# node.net
KiCad netlist of a schematic drawn in EAGLE
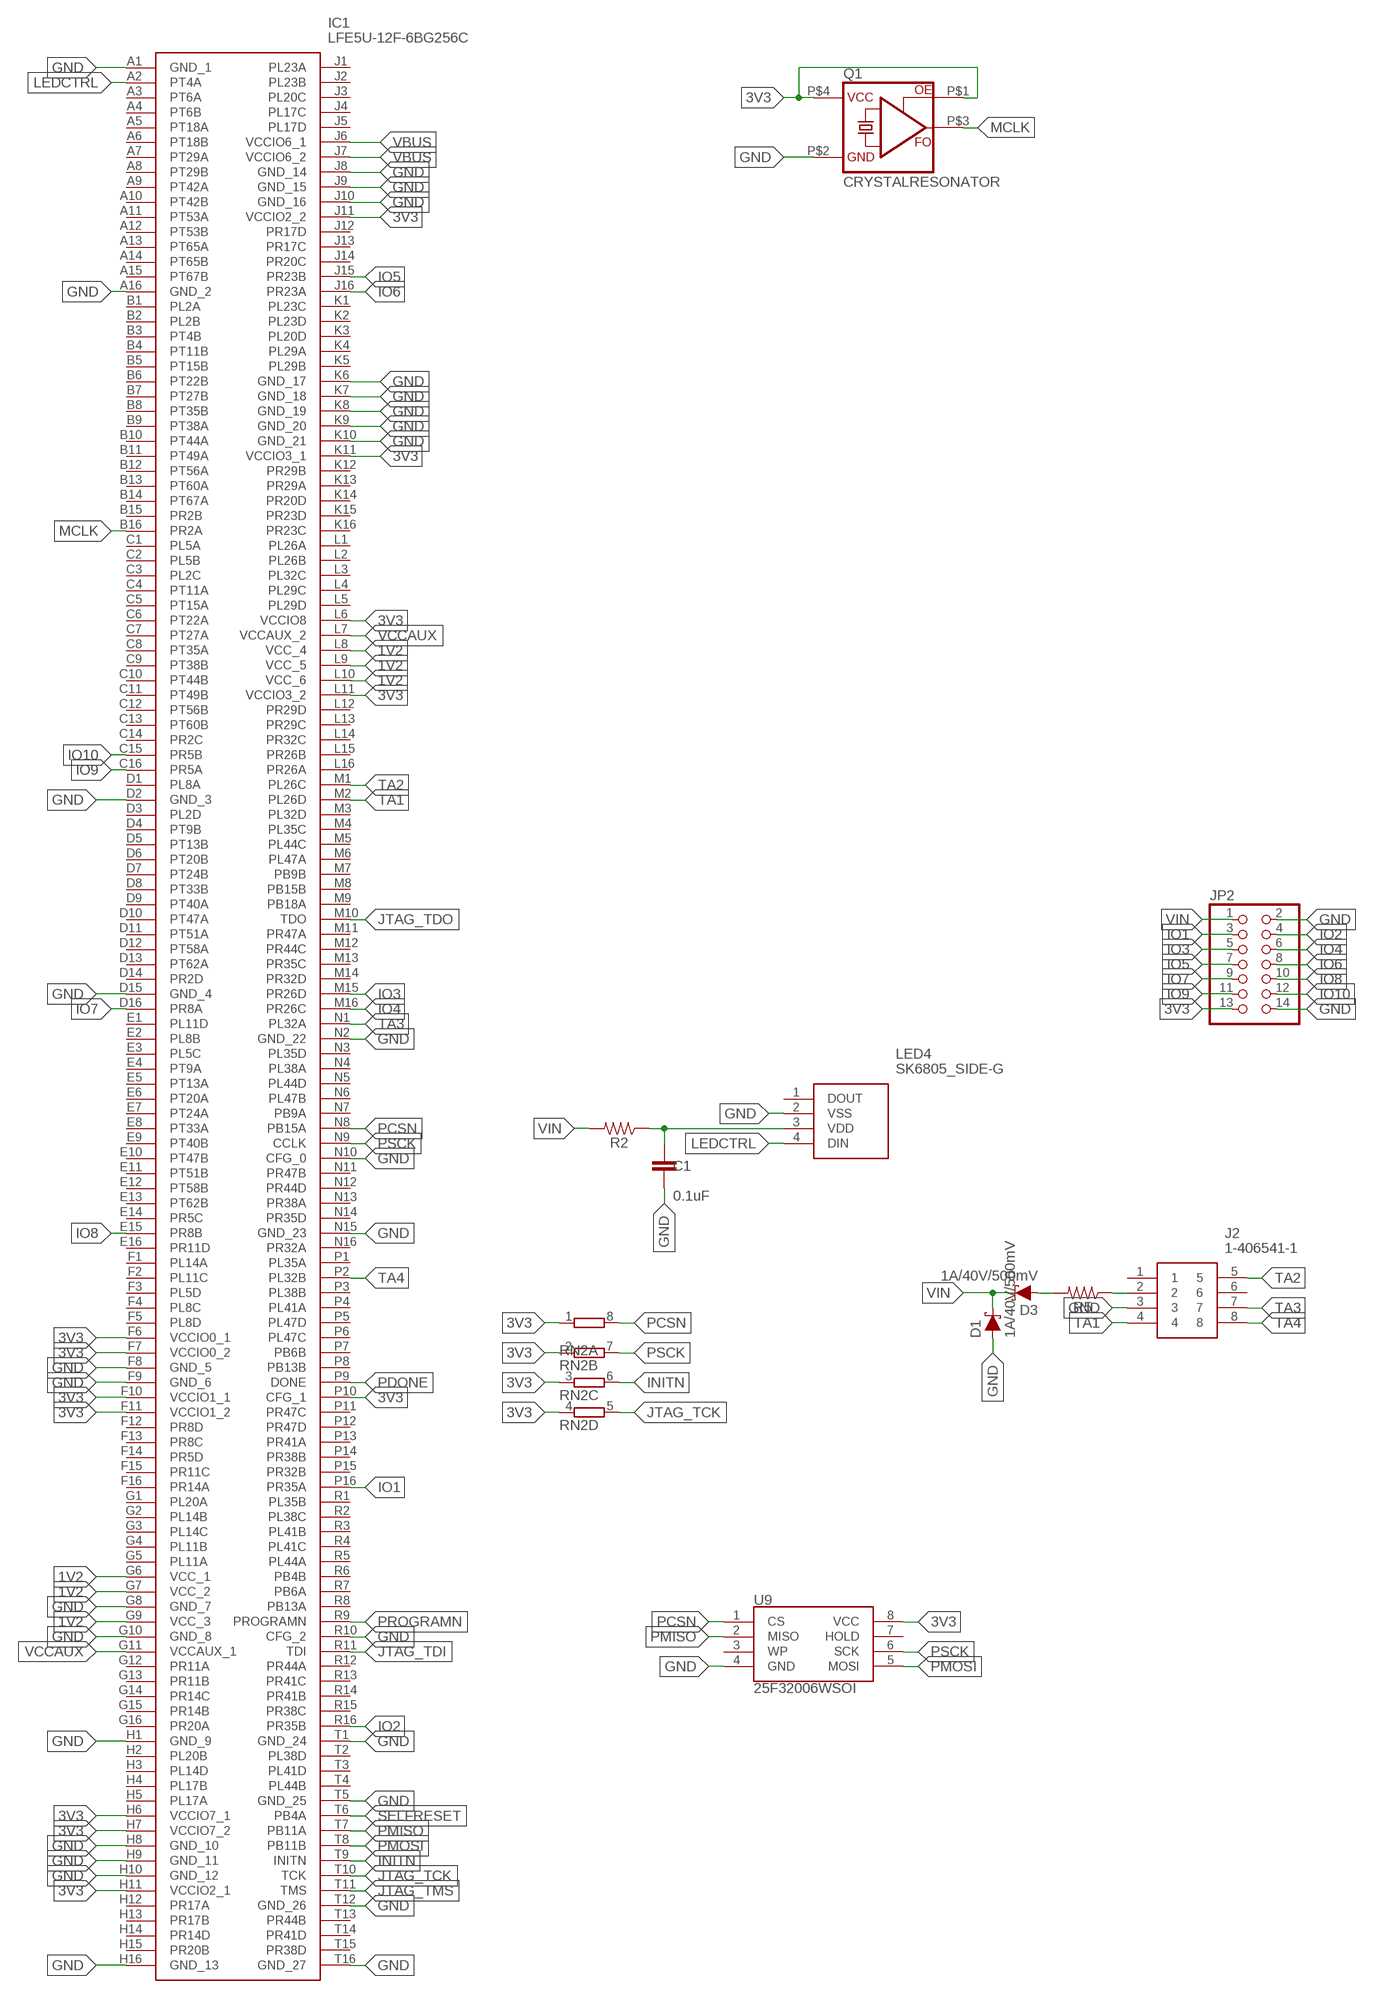
[diagram p0: schematic, sheet 1, part 1 of 2]
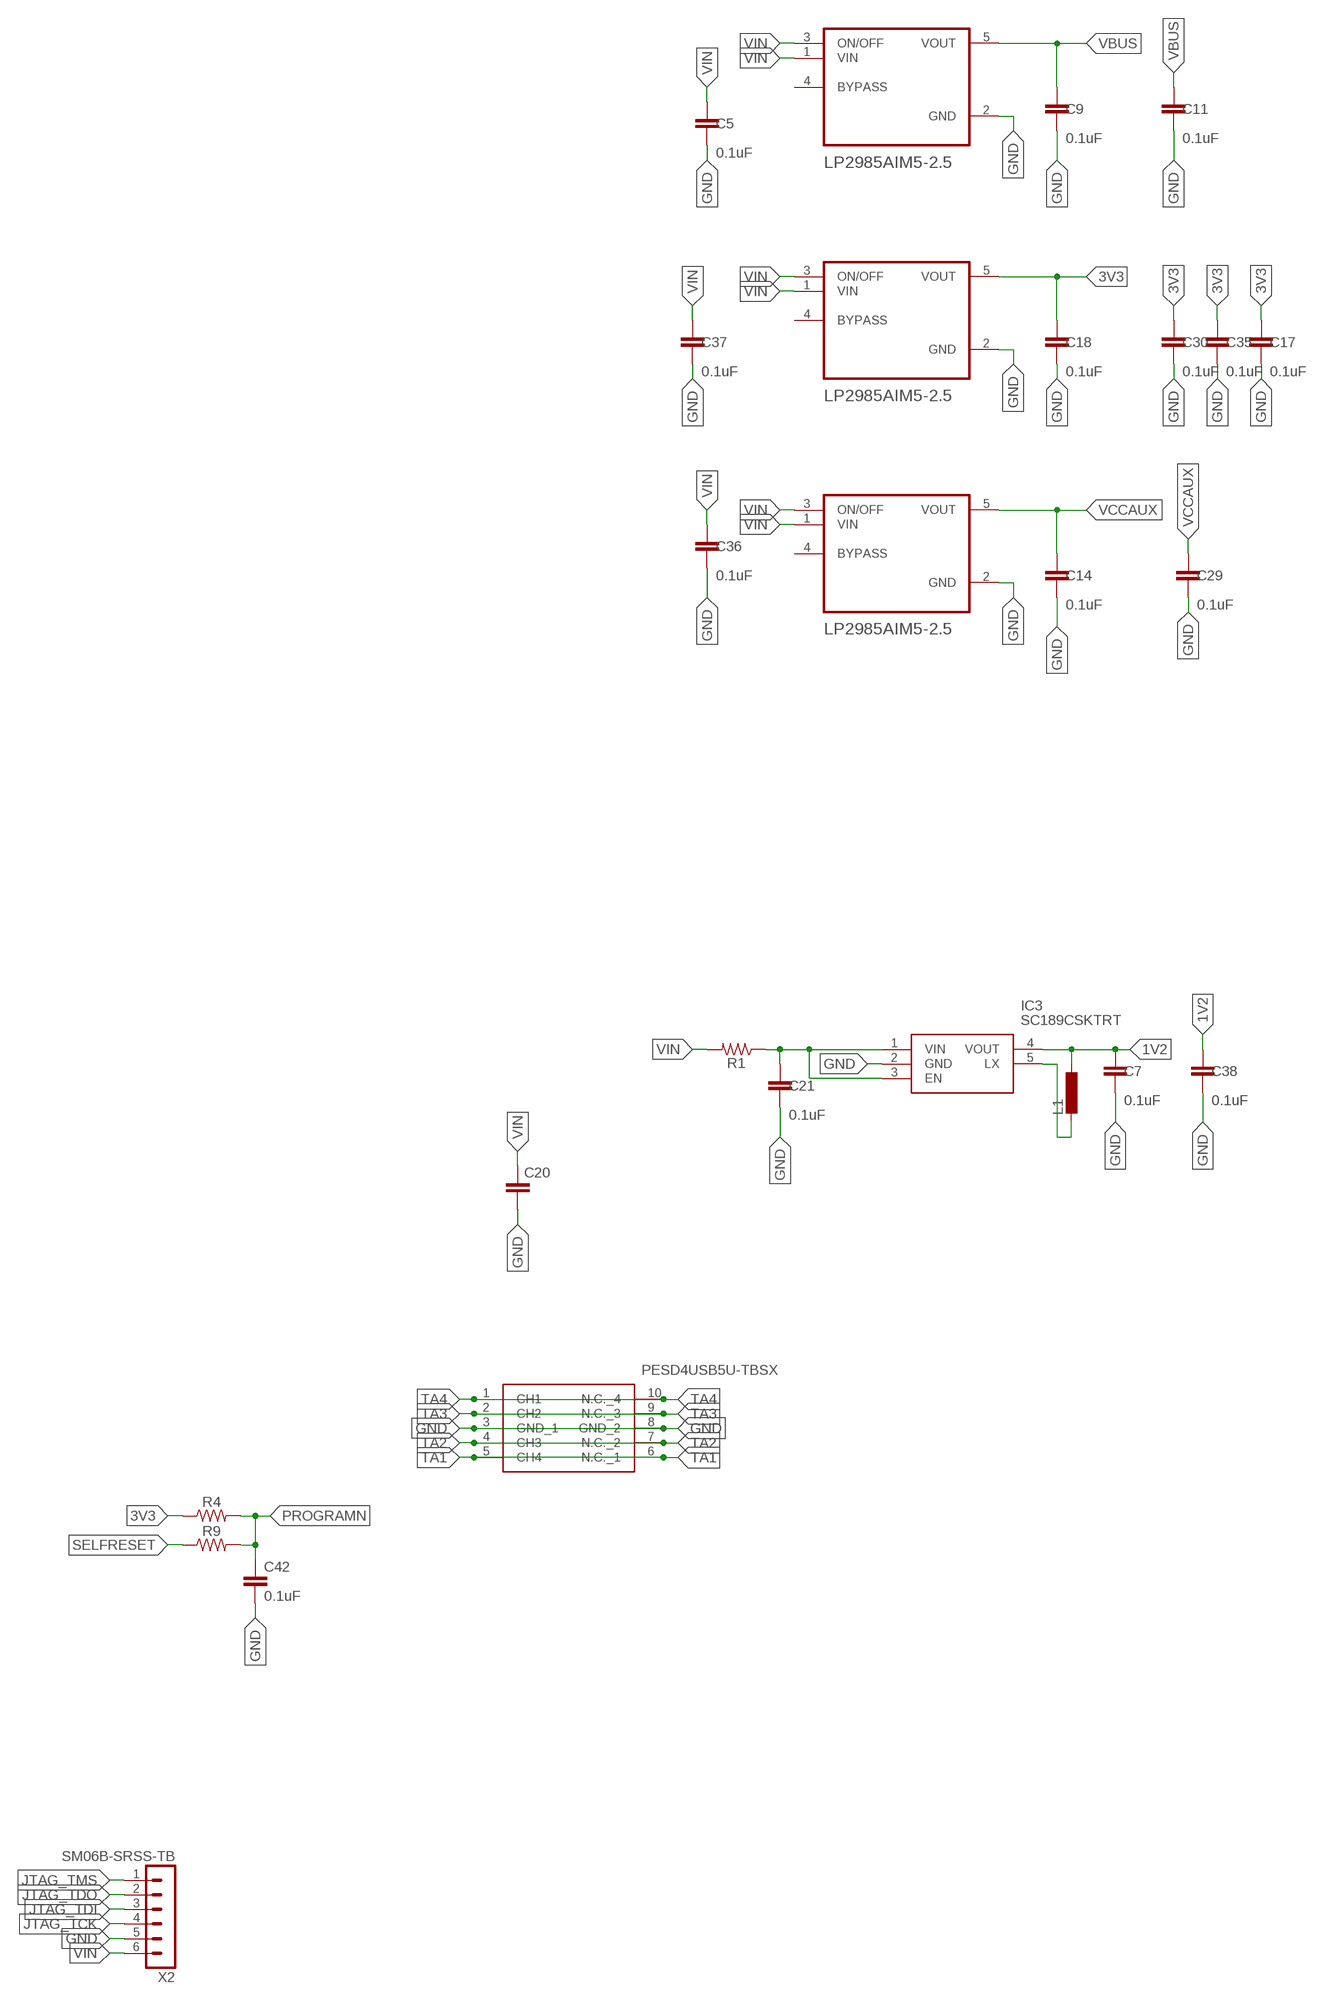
[diagram p1: schematic, sheet 1, part 2 of 2]

(export (version "E")
  (design (tool "Eeschema 10.0.6"))
  (components
    (comp (ref "C1")
      (value "0.1uF")
      (footprint "eagle-import:0603")
      (libsource (lib "eagle-import") (part "0.1UF-0603-25V-5%"))
    )
    (comp (ref "C5")
      (value "0.1uF")
      (footprint "eagle-import:0603")
      (libsource (lib "eagle-import") (part "0.1UF-0603-25V-5%"))
    )
    (comp (ref "C7")
      (value "0.1uF")
      (footprint "eagle-import:0603")
      (libsource (lib "eagle-import") (part "0.1UF-0603-25V-5%"))
    )
    (comp (ref "C9")
      (value "0.1uF")
      (footprint "eagle-import:0603")
      (libsource (lib "eagle-import") (part "0.1UF-0603-25V-5%"))
    )
    (comp (ref "C11")
      (value "0.1uF")
      (footprint "eagle-import:0603")
      (libsource (lib "eagle-import") (part "0.1UF-0603-25V-5%"))
    )
    (comp (ref "C14")
      (value "0.1uF")
      (footprint "eagle-import:0603")
      (libsource (lib "eagle-import") (part "0.1UF-0603-25V-5%"))
    )
    (comp (ref "C17")
      (value "0.1uF")
      (footprint "eagle-import:0603")
      (libsource (lib "eagle-import") (part "0.1UF-0603-25V-5%"))
    )
    (comp (ref "C18")
      (value "0.1uF")
      (footprint "eagle-import:0603")
      (libsource (lib "eagle-import") (part "0.1UF-0603-25V-5%"))
    )
    (comp (ref "C20")
      (value "C-EUC1812")
      (footprint "eagle-import:C1812")
      (libsource (lib "eagle-import") (part "C-EUC1812"))
    )
    (comp (ref "C21")
      (value "0.1uF")
      (footprint "eagle-import:0603")
      (libsource (lib "eagle-import") (part "0.1UF-0603-25V-5%"))
    )
    (comp (ref "C29")
      (value "0.1uF")
      (footprint "eagle-import:0603")
      (libsource (lib "eagle-import") (part "0.1UF-0603-25V-5%"))
    )
    (comp (ref "C30")
      (value "0.1uF")
      (footprint "eagle-import:0603")
      (libsource (lib "eagle-import") (part "0.1UF-0603-25V-5%"))
    )
    (comp (ref "C35")
      (value "0.1uF")
      (footprint "eagle-import:0603")
      (libsource (lib "eagle-import") (part "0.1UF-0603-25V-5%"))
    )
    (comp (ref "C36")
      (value "0.1uF")
      (footprint "eagle-import:0603")
      (libsource (lib "eagle-import") (part "0.1UF-0603-25V-5%"))
    )
    (comp (ref "C37")
      (value "0.1uF")
      (footprint "eagle-import:0603")
      (libsource (lib "eagle-import") (part "0.1UF-0603-25V-5%"))
    )
    (comp (ref "C38")
      (value "0.1uF")
      (footprint "eagle-import:0603")
      (libsource (lib "eagle-import") (part "0.1UF-0603-25V-5%"))
    )
    (comp (ref "C42")
      (value "0.1uF")
      (footprint "eagle-import:0603")
      (libsource (lib "eagle-import") (part "0.1UF-0603-25V-5%"))
    )
    (comp (ref "D1")
      (value "1A/40V/500mV")
      (footprint "eagle-import:SMA-DIODE")
      (libsource (lib "eagle-import") (part "DIODE-SCHOTTKY-SS14"))
    )
    (comp (ref "D3")
      (value "1A/40V/500mV")
      (footprint "eagle-import:SMA-DIODE")
      (libsource (lib "eagle-import") (part "DIODE-SCHOTTKY-SS14"))
    )
    (comp (ref "D10")
      (value "PESD4USB5U-TBSX")
      (footprint "eagle-import:SON50P100X250X80-10N")
      (fields (field (name "MOUSER_PART_NUMBER") "771-PESD4USB5U-TBSX"))
      (libsource (lib "eagle-import") (part "PESD4USB5U-TBSX"))
    )
    (comp (ref "IC1")
      (value "LFE5U-12F-6BG256C")
      (footprint "eagle-import:BGA256C80P16X16_1400X1400X170")
      (fields (field (name "MF") "Lattice Semiconductor"))
      (libsource (lib "eagle-import") (part "LFE5U-12F-6BG256C"))
    )
    (comp (ref "IC3")
      (value "SC189CSKTRT")
      (footprint "eagle-import:SOT95P280X145-5N")
      (fields (field (name "MOUSER_PART_NUMBER") "947-SC189CSKTRT"))
      (libsource (lib "eagle-import") (part "SC189CSKTRT"))
    )
    (comp (ref "J2")
      (value "1-406541-1")
      (footprint "eagle-import:1-406541-1_1")
      (fields (field (name "MOUSER_PART_NUMBER") "571-1-406541-1"))
      (libsource (lib "eagle-import") (part "1-406541-1"))
    )
    (comp (ref "JP2")
      (value "PINHD-2X7")
      (footprint "eagle-import:2X07")
      (libsource (lib "eagle-import") (part "PINHD-2X7"))
    )
    (comp (ref "L1")
      (value "L-EUL3230M")
      (footprint "eagle-import:L3230M")
      (libsource (lib "eagle-import") (part "L-EUL3230M"))
    )
    (comp (ref "LED4")
      (value "SK6805_SIDE-G")
      (footprint "eagle-import:SK6805SIDEG")
      (fields (field (name "MANUFACTURER_PART_NUMBER") "SK6805 SIDE-G"))
      (libsource (lib "eagle-import") (part "SK6805_SIDE-G"))
    )
    (comp (ref "Q1")
      (value "CRYSTALRESONATOR")
      (footprint "eagle-import:XO53X")
      (libsource (lib "eagle-import") (part "CRYSTALRESONATOR"))
    )
    (comp (ref "R1")
      (value "RESISTOR0603")
      (footprint "eagle-import:0603")
      (libsource (lib "eagle-import") (part "RESISTOR0603"))
    )
    (comp (ref "R2")
      (value "RESISTOR0603")
      (footprint "eagle-import:0603")
      (libsource (lib "eagle-import") (part "RESISTOR0603"))
    )
    (comp (ref "R4")
      (value "RESISTOR0603")
      (footprint "eagle-import:0603")
      (libsource (lib "eagle-import") (part "RESISTOR0603"))
    )
    (comp (ref "R5")
      (value "RESISTOR0805")
      (footprint "eagle-import:0805")
      (libsource (lib "eagle-import") (part "RESISTOR0805"))
    )
    (comp (ref "R9")
      (value "RESISTOR0603")
      (footprint "eagle-import:0603")
      (libsource (lib "eagle-import") (part "RESISTOR0603"))
    )
    (comp (ref "RN2")
      (value "4R-NEXBV8V")
      (footprint "eagle-import:EXBV8V")
      (libsource (lib "eagle-import") (part "4R-NEXBV8V"))
    )
    (comp (ref "U1")
      (value "LP2985AIM5-2.5")
      (footprint "eagle-import:SOT95P280X145-5N")
      (fields (field (name "MF") "Texas Instruments") (field (name "MP") "LP2985AIM5-2.5/NOPB"))
      (libsource (lib "eagle-import") (part "LP2985AIM5-2.5"))
    )
    (comp (ref "U2")
      (value "LP2985AIM5-2.5")
      (footprint "eagle-import:SOT95P280X145-5N")
      (fields (field (name "MF") "Texas Instruments") (field (name "MP") "LP2985AIM5-2.5/NOPB"))
      (libsource (lib "eagle-import") (part "LP2985AIM5-2.5"))
    )
    (comp (ref "U6")
      (value "LP2985AIM5-2.5")
      (footprint "eagle-import:SOT95P280X145-5N")
      (fields (field (name "MF") "Texas Instruments") (field (name "MP") "LP2985AIM5-2.5/NOPB"))
      (libsource (lib "eagle-import") (part "LP2985AIM5-2.5"))
    )
    (comp (ref "U9")
      (value "25F32006WSOI")
      (footprint "eagle-import:SO08-EIAJ")
      (libsource (lib "eagle-import") (part "SPI_FLASH-X25XXSMD1"))
    )
    (comp (ref "X2")
      (value "SM06B-SRSS-TB")
      (footprint "eagle-import:SM06B-SRSS-TB")
      (libsource (lib "eagle-import") (part "SM06B-SRSS-TB"))
    )
  )
  (nets
    (net (code "1") (name "1V2") (class "Default")
      (node (ref "C38") (pin "1") (pinfunction "1_1") (pintype "passive"))
      (node (ref "C7") (pin "1") (pinfunction "1_1") (pintype "passive"))
      (node (ref "IC1") (pin "G6") (pinfunction "VCC_1_G6") (pintype "bidirectional"))
      (node (ref "IC1") (pin "G7") (pinfunction "VCC_2_G7") (pintype "bidirectional"))
      (node (ref "IC1") (pin "G9") (pinfunction "VCC_3_G9") (pintype "bidirectional"))
      (node (ref "IC1") (pin "L10") (pinfunction "VCC_6_L10") (pintype "bidirectional"))
      (node (ref "IC1") (pin "L8") (pinfunction "VCC_4_L8") (pintype "bidirectional"))
      (node (ref "IC1") (pin "L9") (pinfunction "VCC_5_L9") (pintype "bidirectional"))
      (node (ref "IC3") (pin "4") (pinfunction "VOUT_4") (pintype "bidirectional"))
      (node (ref "L1") (pin "1") (pinfunction "1_1") (pintype "passive"))
    )
    (net (code "2") (name "3V3") (class "Default")
      (node (ref "C17") (pin "1") (pinfunction "1_1") (pintype "passive"))
      (node (ref "C18") (pin "1") (pinfunction "1_1") (pintype "passive"))
      (node (ref "C30") (pin "1") (pinfunction "1_1") (pintype "passive"))
      (node (ref "C35") (pin "1") (pinfunction "1_1") (pintype "passive"))
      (node (ref "IC1") (pin "F10") (pinfunction "VCCIO1_1_F10") (pintype "bidirectional"))
      (node (ref "IC1") (pin "F11") (pinfunction "VCCIO1_2_F11") (pintype "bidirectional"))
      (node (ref "IC1") (pin "F6") (pinfunction "VCCIO0_1_F6") (pintype "bidirectional"))
      (node (ref "IC1") (pin "F7") (pinfunction "VCCIO0_2_F7") (pintype "bidirectional"))
      (node (ref "IC1") (pin "H11") (pinfunction "VCCIO2_1_H11") (pintype "bidirectional"))
      (node (ref "IC1") (pin "H6") (pinfunction "VCCIO7_1_H6") (pintype "bidirectional"))
      (node (ref "IC1") (pin "H7") (pinfunction "VCCIO7_2_H7") (pintype "bidirectional"))
      (node (ref "IC1") (pin "J11") (pinfunction "VCCIO2_2_J11") (pintype "bidirectional"))
      (node (ref "IC1") (pin "K11") (pinfunction "VCCIO3_1_K11") (pintype "bidirectional"))
      (node (ref "IC1") (pin "L11") (pinfunction "VCCIO3_2_L11") (pintype "bidirectional"))
      (node (ref "IC1") (pin "L6") (pinfunction "VCCIO8_L6") (pintype "bidirectional"))
      (node (ref "IC1") (pin "P10") (pinfunction "CFG_1_P10") (pintype "bidirectional"))
      (node (ref "JP2") (pin "13") (pinfunction "13_13") (pintype "passive"))
      (node (ref "Q1") (pin "P$1") (pinfunction "OE_P$1") (pintype "input"))
      (node (ref "Q1") (pin "P$4") (pinfunction "VCC_P$4") (pintype "power_in"))
      (node (ref "R4") (pin "1") (pinfunction "1_1") (pintype "passive"))
      (node (ref "RN2") (pin "1") (pinfunction "1_1") (pintype "passive"))
      (node (ref "RN2") (pin "2") (pinfunction "1_2") (pintype "passive"))
      (node (ref "RN2") (pin "3") (pinfunction "1_3") (pintype "passive"))
      (node (ref "RN2") (pin "4") (pinfunction "1_4") (pintype "passive"))
      (node (ref "U2") (pin "5") (pinfunction "VOUT_5") (pintype "output"))
      (node (ref "U9") (pin "8") (pinfunction "VCC_8") (pintype "power_in"))
    )
    (net (code "3") (name "GND") (class "Default")
      (node (ref "C1") (pin "2") (pinfunction "2_2") (pintype "passive"))
      (node (ref "C11") (pin "2") (pinfunction "2_2") (pintype "passive"))
      (node (ref "C14") (pin "2") (pinfunction "2_2") (pintype "passive"))
      (node (ref "C17") (pin "2") (pinfunction "2_2") (pintype "passive"))
      (node (ref "C18") (pin "2") (pinfunction "2_2") (pintype "passive"))
      (node (ref "C20") (pin "2") (pinfunction "2_2") (pintype "passive"))
      (node (ref "C21") (pin "2") (pinfunction "2_2") (pintype "passive"))
      (node (ref "C29") (pin "2") (pinfunction "2_2") (pintype "passive"))
      (node (ref "C30") (pin "2") (pinfunction "2_2") (pintype "passive"))
      (node (ref "C35") (pin "2") (pinfunction "2_2") (pintype "passive"))
      (node (ref "C36") (pin "2") (pinfunction "2_2") (pintype "passive"))
      (node (ref "C37") (pin "2") (pinfunction "2_2") (pintype "passive"))
      (node (ref "C38") (pin "2") (pinfunction "2_2") (pintype "passive"))
      (node (ref "C42") (pin "2") (pinfunction "2_2") (pintype "passive"))
      (node (ref "C5") (pin "2") (pinfunction "2_2") (pintype "passive"))
      (node (ref "C7") (pin "2") (pinfunction "2_2") (pintype "passive"))
      (node (ref "C9") (pin "2") (pinfunction "2_2") (pintype "passive"))
      (node (ref "D1") (pin "A") (pinfunction "A_A") (pintype "passive"))
      (node (ref "D10") (pin "3") (pinfunction "GND_1_3") (pintype "bidirectional"))
      (node (ref "D10") (pin "8") (pinfunction "GND_2_8") (pintype "bidirectional"))
      (node (ref "IC1") (pin "A1") (pinfunction "GND_1_A1") (pintype "bidirectional"))
      (node (ref "IC1") (pin "A16") (pinfunction "GND_2_A16") (pintype "bidirectional"))
      (node (ref "IC1") (pin "D15") (pinfunction "GND_4_D15") (pintype "bidirectional"))
      (node (ref "IC1") (pin "D2") (pinfunction "GND_3_D2") (pintype "bidirectional"))
      (node (ref "IC1") (pin "F8") (pinfunction "GND_5_F8") (pintype "bidirectional"))
      (node (ref "IC1") (pin "F9") (pinfunction "GND_6_F9") (pintype "bidirectional"))
      (node (ref "IC1") (pin "G10") (pinfunction "GND_8_G10") (pintype "bidirectional"))
      (node (ref "IC1") (pin "G8") (pinfunction "GND_7_G8") (pintype "bidirectional"))
      (node (ref "IC1") (pin "H1") (pinfunction "GND_9_H1") (pintype "bidirectional"))
      (node (ref "IC1") (pin "H10") (pinfunction "GND_12_H10") (pintype "bidirectional"))
      (node (ref "IC1") (pin "H16") (pinfunction "GND_13_H16") (pintype "bidirectional"))
      (node (ref "IC1") (pin "H8") (pinfunction "GND_10_H8") (pintype "bidirectional"))
      (node (ref "IC1") (pin "H9") (pinfunction "GND_11_H9") (pintype "bidirectional"))
      (node (ref "IC1") (pin "J10") (pinfunction "GND_16_J10") (pintype "bidirectional"))
      (node (ref "IC1") (pin "J8") (pinfunction "GND_14_J8") (pintype "bidirectional"))
      (node (ref "IC1") (pin "J9") (pinfunction "GND_15_J9") (pintype "bidirectional"))
      (node (ref "IC1") (pin "K10") (pinfunction "GND_21_K10") (pintype "bidirectional"))
      (node (ref "IC1") (pin "K6") (pinfunction "GND_17_K6") (pintype "bidirectional"))
      (node (ref "IC1") (pin "K7") (pinfunction "GND_18_K7") (pintype "bidirectional"))
      (node (ref "IC1") (pin "K8") (pinfunction "GND_19_K8") (pintype "bidirectional"))
      (node (ref "IC1") (pin "K9") (pinfunction "GND_20_K9") (pintype "bidirectional"))
      (node (ref "IC1") (pin "N10") (pinfunction "CFG_0_N10") (pintype "bidirectional"))
      (node (ref "IC1") (pin "N15") (pinfunction "GND_23_N15") (pintype "bidirectional"))
      (node (ref "IC1") (pin "N2") (pinfunction "GND_22_N2") (pintype "bidirectional"))
      (node (ref "IC1") (pin "R10") (pinfunction "CFG_2_R10") (pintype "bidirectional"))
      (node (ref "IC1") (pin "T1") (pinfunction "GND_24_T1") (pintype "bidirectional"))
      (node (ref "IC1") (pin "T12") (pinfunction "GND_26_T12") (pintype "bidirectional"))
      (node (ref "IC1") (pin "T16") (pinfunction "GND_27_T16") (pintype "bidirectional"))
      (node (ref "IC1") (pin "T5") (pinfunction "GND_25_T5") (pintype "bidirectional"))
      (node (ref "IC3") (pin "2") (pinfunction "GND_2") (pintype "bidirectional"))
      (node (ref "J2") (pin "3") (pinfunction "3_3") (pintype "bidirectional"))
      (node (ref "JP2") (pin "14") (pinfunction "14_14") (pintype "passive"))
      (node (ref "JP2") (pin "2") (pinfunction "2_2") (pintype "passive"))
      (node (ref "LED4") (pin "2") (pinfunction "VSS_2") (pintype "bidirectional"))
      (node (ref "Q1") (pin "P$2") (pinfunction "GND_P$2") (pintype "power_in"))
      (node (ref "U1") (pin "2") (pinfunction "GND_2") (pintype "power_in"))
      (node (ref "U2") (pin "2") (pinfunction "GND_2") (pintype "power_in"))
      (node (ref "U6") (pin "2") (pinfunction "GND_2") (pintype "power_in"))
      (node (ref "U9") (pin "4") (pinfunction "GND_4") (pintype "power_in"))
      (node (ref "X2") (pin "5") (pinfunction "5_5") (pintype "passive"))
    )
    (net (code "4") (name "INITN") (class "Default")
      (node (ref "IC1") (pin "T9") (pinfunction "INITN_T9") (pintype "bidirectional"))
      (node (ref "RN2") (pin "6") (pinfunction "2_6") (pintype "passive"))
    )
    (net (code "5") (name "IO1") (class "Default")
      (node (ref "IC1") (pin "P16") (pinfunction "PR35A_P16") (pintype "bidirectional"))
      (node (ref "JP2") (pin "3") (pinfunction "3_3") (pintype "passive"))
    )
    (net (code "6") (name "IO2") (class "Default")
      (node (ref "IC1") (pin "R16") (pinfunction "PR35B_R16") (pintype "bidirectional"))
      (node (ref "JP2") (pin "4") (pinfunction "4_4") (pintype "passive"))
    )
    (net (code "7") (name "IO3") (class "Default")
      (node (ref "IC1") (pin "M15") (pinfunction "PR26D_M15") (pintype "bidirectional"))
      (node (ref "JP2") (pin "5") (pinfunction "5_5") (pintype "passive"))
    )
    (net (code "8") (name "IO4") (class "Default")
      (node (ref "IC1") (pin "M16") (pinfunction "PR26C_M16") (pintype "bidirectional"))
      (node (ref "JP2") (pin "6") (pinfunction "6_6") (pintype "passive"))
    )
    (net (code "9") (name "IO5") (class "Default")
      (node (ref "IC1") (pin "J15") (pinfunction "PR23B_J15") (pintype "bidirectional"))
      (node (ref "JP2") (pin "7") (pinfunction "7_7") (pintype "passive"))
    )
    (net (code "10") (name "IO6") (class "Default")
      (node (ref "IC1") (pin "J16") (pinfunction "PR23A_J16") (pintype "bidirectional"))
      (node (ref "JP2") (pin "8") (pinfunction "8_8") (pintype "passive"))
    )
    (net (code "11") (name "IO7") (class "Default")
      (node (ref "IC1") (pin "D16") (pinfunction "PR8A_D16") (pintype "bidirectional"))
      (node (ref "JP2") (pin "9") (pinfunction "9_9") (pintype "passive"))
    )
    (net (code "12") (name "IO8") (class "Default")
      (node (ref "IC1") (pin "E15") (pinfunction "PR8B_E15") (pintype "bidirectional"))
      (node (ref "JP2") (pin "10") (pinfunction "10_10") (pintype "passive"))
    )
    (net (code "13") (name "IO9") (class "Default")
      (node (ref "IC1") (pin "C16") (pinfunction "PR5A_C16") (pintype "bidirectional"))
      (node (ref "JP2") (pin "11") (pinfunction "11_11") (pintype "passive"))
    )
    (net (code "14") (name "IO10") (class "Default")
      (node (ref "IC1") (pin "C15") (pinfunction "PR5B_C15") (pintype "bidirectional"))
      (node (ref "JP2") (pin "12") (pinfunction "12_12") (pintype "passive"))
    )
    (net (code "15") (name "JTAG_TCK") (class "Default")
      (node (ref "IC1") (pin "T10") (pinfunction "TCK_T10") (pintype "bidirectional"))
      (node (ref "RN2") (pin "5") (pinfunction "2_5") (pintype "passive"))
      (node (ref "X2") (pin "4") (pinfunction "4_4") (pintype "passive"))
    )
    (net (code "16") (name "JTAG_TDI") (class "Default")
      (node (ref "IC1") (pin "R11") (pinfunction "TDI_R11") (pintype "bidirectional"))
      (node (ref "X2") (pin "3") (pinfunction "3_3") (pintype "passive"))
    )
    (net (code "17") (name "JTAG_TDO") (class "Default")
      (node (ref "IC1") (pin "M10") (pinfunction "TDO_M10") (pintype "bidirectional"))
      (node (ref "X2") (pin "2") (pinfunction "2_2") (pintype "passive"))
    )
    (net (code "18") (name "JTAG_TMS") (class "Default")
      (node (ref "IC1") (pin "T11") (pinfunction "TMS_T11") (pintype "bidirectional"))
      (node (ref "X2") (pin "1") (pinfunction "1_1") (pintype "passive"))
    )
    (net (code "19") (name "LEDCTRL") (class "Default")
      (node (ref "IC1") (pin "A2") (pinfunction "PT4A_A2") (pintype "bidirectional"))
      (node (ref "LED4") (pin "4") (pinfunction "DIN_4") (pintype "bidirectional"))
    )
    (net (code "20") (name "MCLK") (class "Default")
      (node (ref "IC1") (pin "B16") (pinfunction "PR2A_B16") (pintype "bidirectional"))
      (node (ref "Q1") (pin "P$3") (pinfunction "FO_P$3") (pintype "output"))
    )
    (net (code "21") (name "Net-(D3-PadA)") (class "Default")
      (node (ref "D3") (pin "A") (pinfunction "A_A") (pintype "passive"))
      (node (ref "R5") (pin "2") (pinfunction "2_2") (pintype "passive"))
    )
    (net (code "22") (name "Net-(IC3-EN)") (class "Default")
      (node (ref "C21") (pin "1") (pinfunction "1_1") (pintype "passive"))
      (node (ref "IC3") (pin "1") (pinfunction "VIN_1") (pintype "bidirectional"))
      (node (ref "IC3") (pin "3") (pinfunction "EN_3") (pintype "bidirectional"))
      (node (ref "R1") (pin "1") (pinfunction "1_1") (pintype "passive"))
    )
    (net (code "23") (name "Net-(IC3-LX)") (class "Default")
      (node (ref "IC3") (pin "5") (pinfunction "LX_5") (pintype "bidirectional"))
      (node (ref "L1") (pin "2") (pinfunction "2_2") (pintype "passive"))
    )
    (net (code "24") (name "Net-(J2-Pad2)") (class "Default")
      (node (ref "J2") (pin "2") (pinfunction "2_2") (pintype "bidirectional"))
      (node (ref "R5") (pin "1") (pinfunction "1_1") (pintype "passive"))
    )
    (net (code "25") (name "Net-(LED4-VDD)") (class "Default")
      (node (ref "C1") (pin "1") (pinfunction "1_1") (pintype "passive"))
      (node (ref "LED4") (pin "3") (pinfunction "VDD_3") (pintype "bidirectional"))
      (node (ref "R2") (pin "1") (pinfunction "1_1") (pintype "passive"))
    )
    (net (code "26") (name "PCSN") (class "Default")
      (node (ref "IC1") (pin "N8") (pinfunction "PB15A_N8") (pintype "bidirectional"))
      (node (ref "RN2") (pin "8") (pinfunction "2_8") (pintype "passive"))
      (node (ref "U9") (pin "1") (pinfunction "CS_1") (pintype "bidirectional"))
    )
    (net (code "27") (name "PDONE") (class "Default")
      (node (ref "IC1") (pin "P9") (pinfunction "DONE_P9") (pintype "bidirectional"))
    )
    (net (code "28") (name "PMISO") (class "Default")
      (node (ref "IC1") (pin "T7") (pinfunction "PB11A_T7") (pintype "bidirectional"))
      (node (ref "U9") (pin "2") (pinfunction "MISO_2") (pintype "bidirectional"))
    )
    (net (code "29") (name "PMOSI") (class "Default")
      (node (ref "IC1") (pin "T8") (pinfunction "PB11B_T8") (pintype "bidirectional"))
      (node (ref "U9") (pin "5") (pinfunction "MOSI_5") (pintype "bidirectional"))
    )
    (net (code "30") (name "PROGRAMN") (class "Default")
      (node (ref "C42") (pin "1") (pinfunction "1_1") (pintype "passive"))
      (node (ref "IC1") (pin "R9") (pinfunction "PROGRAMN_R9") (pintype "bidirectional"))
      (node (ref "R4") (pin "2") (pinfunction "2_2") (pintype "passive"))
      (node (ref "R9") (pin "2") (pinfunction "2_2") (pintype "passive"))
    )
    (net (code "31") (name "PSCK") (class "Default")
      (node (ref "IC1") (pin "N9") (pinfunction "CCLK_N9") (pintype "bidirectional"))
      (node (ref "RN2") (pin "7") (pinfunction "2_7") (pintype "passive"))
      (node (ref "U9") (pin "6") (pinfunction "SCK_6") (pintype "bidirectional"))
    )
    (net (code "32") (name "SELFRESET") (class "Default")
      (node (ref "IC1") (pin "T6") (pinfunction "PB4A_T6") (pintype "bidirectional"))
      (node (ref "R9") (pin "1") (pinfunction "1_1") (pintype "passive"))
    )
    (net (code "33") (name "TA1") (class "Default")
      (node (ref "D10") (pin "5") (pinfunction "CH4_5") (pintype "bidirectional"))
      (node (ref "D10") (pin "6") (pinfunction "N.C._1_6") (pintype "bidirectional"))
      (node (ref "IC1") (pin "M2") (pinfunction "PL26D_M2") (pintype "bidirectional"))
      (node (ref "J2") (pin "4") (pinfunction "4_4") (pintype "bidirectional"))
    )
    (net (code "34") (name "TA2") (class "Default")
      (node (ref "D10") (pin "4") (pinfunction "CH3_4") (pintype "bidirectional"))
      (node (ref "D10") (pin "7") (pinfunction "N.C._2_7") (pintype "bidirectional"))
      (node (ref "IC1") (pin "M1") (pinfunction "PL26C_M1") (pintype "bidirectional"))
      (node (ref "J2") (pin "5") (pinfunction "5_5") (pintype "bidirectional"))
    )
    (net (code "35") (name "TA3") (class "Default")
      (node (ref "D10") (pin "2") (pinfunction "CH2_2") (pintype "bidirectional"))
      (node (ref "D10") (pin "9") (pinfunction "N.C._3_9") (pintype "bidirectional"))
      (node (ref "IC1") (pin "N1") (pinfunction "PL32A_N1") (pintype "bidirectional"))
      (node (ref "J2") (pin "7") (pinfunction "7_7") (pintype "bidirectional"))
    )
    (net (code "36") (name "TA4") (class "Default")
      (node (ref "D10") (pin "1") (pinfunction "CH1_1") (pintype "bidirectional"))
      (node (ref "D10") (pin "10") (pinfunction "N.C._4_10") (pintype "bidirectional"))
      (node (ref "IC1") (pin "P2") (pinfunction "PL32B_P2") (pintype "bidirectional"))
      (node (ref "J2") (pin "8") (pinfunction "8_8") (pintype "bidirectional"))
    )
    (net (code "37") (name "VBUS") (class "Default")
      (node (ref "C11") (pin "1") (pinfunction "1_1") (pintype "passive"))
      (node (ref "C9") (pin "1") (pinfunction "1_1") (pintype "passive"))
      (node (ref "IC1") (pin "J6") (pinfunction "VCCIO6_1_J6") (pintype "bidirectional"))
      (node (ref "IC1") (pin "J7") (pinfunction "VCCIO6_2_J7") (pintype "bidirectional"))
      (node (ref "U1") (pin "5") (pinfunction "VOUT_5") (pintype "output"))
    )
    (net (code "38") (name "VCCAUX") (class "Default")
      (node (ref "C14") (pin "1") (pinfunction "1_1") (pintype "passive"))
      (node (ref "C29") (pin "1") (pinfunction "1_1") (pintype "passive"))
      (node (ref "IC1") (pin "G11") (pinfunction "VCCAUX_1_G11") (pintype "bidirectional"))
      (node (ref "IC1") (pin "L7") (pinfunction "VCCAUX_2_L7") (pintype "bidirectional"))
      (node (ref "U6") (pin "5") (pinfunction "VOUT_5") (pintype "output"))
    )
    (net (code "39") (name "VIN") (class "Default")
      (node (ref "C20") (pin "1") (pinfunction "1_1") (pintype "passive"))
      (node (ref "C36") (pin "1") (pinfunction "1_1") (pintype "passive"))
      (node (ref "C37") (pin "1") (pinfunction "1_1") (pintype "passive"))
      (node (ref "C5") (pin "1") (pinfunction "1_1") (pintype "passive"))
      (node (ref "D1") (pin "C") (pinfunction "C_C") (pintype "passive"))
      (node (ref "D3") (pin "C") (pinfunction "C_C") (pintype "passive"))
      (node (ref "JP2") (pin "1") (pinfunction "1_1") (pintype "passive"))
      (node (ref "R1") (pin "2") (pinfunction "2_2") (pintype "passive"))
      (node (ref "R2") (pin "2") (pinfunction "2_2") (pintype "passive"))
      (node (ref "U1") (pin "1") (pinfunction "VIN_1") (pintype "input"))
      (node (ref "U1") (pin "3") (pinfunction "ON/OFF_3") (pintype "input"))
      (node (ref "U2") (pin "1") (pinfunction "VIN_1") (pintype "input"))
      (node (ref "U2") (pin "3") (pinfunction "ON/OFF_3") (pintype "input"))
      (node (ref "U6") (pin "1") (pinfunction "VIN_1") (pintype "input"))
      (node (ref "U6") (pin "3") (pinfunction "ON/OFF_3") (pintype "input"))
      (node (ref "X2") (pin "6") (pinfunction "6_6") (pintype "passive"))
    )
    (net (code "40") (name "unconnected-(IC1-PB4B-PadR6)") (class "Default")
      (node (ref "IC1") (pin "R6") (pinfunction "PB4B_R6") (pintype "bidirectional"))
    )
    (net (code "41") (name "unconnected-(IC1-PB6A-PadR7)") (class "Default")
      (node (ref "IC1") (pin "R7") (pinfunction "PB6A_R7") (pintype "bidirectional"))
    )
    (net (code "42") (name "unconnected-(IC1-PB6B-PadP7)") (class "Default")
      (node (ref "IC1") (pin "P7") (pinfunction "PB6B_P7") (pintype "bidirectional"))
    )
    (net (code "43") (name "unconnected-(IC1-PB9A-PadN7)") (class "Default")
      (node (ref "IC1") (pin "N7") (pinfunction "PB9A_N7") (pintype "bidirectional"))
    )
    (net (code "44") (name "unconnected-(IC1-PB9B-PadM7)") (class "Default")
      (node (ref "IC1") (pin "M7") (pinfunction "PB9B_M7") (pintype "bidirectional"))
    )
    (net (code "45") (name "unconnected-(IC1-PB13A-PadR8)") (class "Default")
      (node (ref "IC1") (pin "R8") (pinfunction "PB13A_R8") (pintype "bidirectional"))
    )
    (net (code "46") (name "unconnected-(IC1-PB13B-PadP8)") (class "Default")
      (node (ref "IC1") (pin "P8") (pinfunction "PB13B_P8") (pintype "bidirectional"))
    )
    (net (code "47") (name "unconnected-(IC1-PB15B-PadM8)") (class "Default")
      (node (ref "IC1") (pin "M8") (pinfunction "PB15B_M8") (pintype "bidirectional"))
    )
    (net (code "48") (name "unconnected-(IC1-PB18A-PadM9)") (class "Default")
      (node (ref "IC1") (pin "M9") (pinfunction "PB18A_M9") (pintype "bidirectional"))
    )
    (net (code "49") (name "unconnected-(IC1-PL2A-PadB1)") (class "Default")
      (node (ref "IC1") (pin "B1") (pinfunction "PL2A_B1") (pintype "bidirectional"))
    )
    (net (code "50") (name "unconnected-(IC1-PL2B-PadB2)") (class "Default")
      (node (ref "IC1") (pin "B2") (pinfunction "PL2B_B2") (pintype "bidirectional"))
    )
    (net (code "51") (name "unconnected-(IC1-PL2C-PadC3)") (class "Default")
      (node (ref "IC1") (pin "C3") (pinfunction "PL2C_C3") (pintype "bidirectional"))
    )
    (net (code "52") (name "unconnected-(IC1-PL2D-PadD3)") (class "Default")
      (node (ref "IC1") (pin "D3") (pinfunction "PL2D_D3") (pintype "bidirectional"))
    )
    (net (code "53") (name "unconnected-(IC1-PL5A-PadC1)") (class "Default")
      (node (ref "IC1") (pin "C1") (pinfunction "PL5A_C1") (pintype "bidirectional"))
    )
    (net (code "54") (name "unconnected-(IC1-PL5B-PadC2)") (class "Default")
      (node (ref "IC1") (pin "C2") (pinfunction "PL5B_C2") (pintype "bidirectional"))
    )
    (net (code "55") (name "unconnected-(IC1-PL5C-PadE3)") (class "Default")
      (node (ref "IC1") (pin "E3") (pinfunction "PL5C_E3") (pintype "bidirectional"))
    )
    (net (code "56") (name "unconnected-(IC1-PL5D-PadF3)") (class "Default")
      (node (ref "IC1") (pin "F3") (pinfunction "PL5D_F3") (pintype "bidirectional"))
    )
    (net (code "57") (name "unconnected-(IC1-PL8A-PadD1)") (class "Default")
      (node (ref "IC1") (pin "D1") (pinfunction "PL8A_D1") (pintype "bidirectional"))
    )
    (net (code "58") (name "unconnected-(IC1-PL8B-PadE2)") (class "Default")
      (node (ref "IC1") (pin "E2") (pinfunction "PL8B_E2") (pintype "bidirectional"))
    )
    (net (code "59") (name "unconnected-(IC1-PL8C-PadF4)") (class "Default")
      (node (ref "IC1") (pin "F4") (pinfunction "PL8C_F4") (pintype "bidirectional"))
    )
    (net (code "60") (name "unconnected-(IC1-PL8D-PadF5)") (class "Default")
      (node (ref "IC1") (pin "F5") (pinfunction "PL8D_F5") (pintype "bidirectional"))
    )
    (net (code "61") (name "unconnected-(IC1-PL11A-PadG5)") (class "Default")
      (node (ref "IC1") (pin "G5") (pinfunction "PL11A_G5") (pintype "bidirectional"))
    )
    (net (code "62") (name "unconnected-(IC1-PL11B-PadG4)") (class "Default")
      (node (ref "IC1") (pin "G4") (pinfunction "PL11B_G4") (pintype "bidirectional"))
    )
    (net (code "63") (name "unconnected-(IC1-PL11C-PadF2)") (class "Default")
      (node (ref "IC1") (pin "F2") (pinfunction "PL11C_F2") (pintype "bidirectional"))
    )
    (net (code "64") (name "unconnected-(IC1-PL11D-PadE1)") (class "Default")
      (node (ref "IC1") (pin "E1") (pinfunction "PL11D_E1") (pintype "bidirectional"))
    )
    (net (code "65") (name "unconnected-(IC1-PL14A-PadF1)") (class "Default")
      (node (ref "IC1") (pin "F1") (pinfunction "PL14A_F1") (pintype "bidirectional"))
    )
    (net (code "66") (name "unconnected-(IC1-PL14B-PadG2)") (class "Default")
      (node (ref "IC1") (pin "G2") (pinfunction "PL14B_G2") (pintype "bidirectional"))
    )
    (net (code "67") (name "unconnected-(IC1-PL14C-PadG3)") (class "Default")
      (node (ref "IC1") (pin "G3") (pinfunction "PL14C_G3") (pintype "bidirectional"))
    )
    (net (code "68") (name "unconnected-(IC1-PL14D-PadH3)") (class "Default")
      (node (ref "IC1") (pin "H3") (pinfunction "PL14D_H3") (pintype "bidirectional"))
    )
    (net (code "69") (name "unconnected-(IC1-PL17A-PadH5)") (class "Default")
      (node (ref "IC1") (pin "H5") (pinfunction "PL17A_H5") (pintype "bidirectional"))
    )
    (net (code "70") (name "unconnected-(IC1-PL17B-PadH4)") (class "Default")
      (node (ref "IC1") (pin "H4") (pinfunction "PL17B_H4") (pintype "bidirectional"))
    )
    (net (code "71") (name "unconnected-(IC1-PL17C-PadJ4)") (class "Default")
      (node (ref "IC1") (pin "J4") (pinfunction "PL17C_J4") (pintype "bidirectional"))
    )
    (net (code "72") (name "unconnected-(IC1-PL17D-PadJ5)") (class "Default")
      (node (ref "IC1") (pin "J5") (pinfunction "PL17D_J5") (pintype "bidirectional"))
    )
    (net (code "73") (name "unconnected-(IC1-PL20A-PadG1)") (class "Default")
      (node (ref "IC1") (pin "G1") (pinfunction "PL20A_G1") (pintype "bidirectional"))
    )
    (net (code "74") (name "unconnected-(IC1-PL20B-PadH2)") (class "Default")
      (node (ref "IC1") (pin "H2") (pinfunction "PL20B_H2") (pintype "bidirectional"))
    )
    (net (code "75") (name "unconnected-(IC1-PL20C-PadJ3)") (class "Default")
      (node (ref "IC1") (pin "J3") (pinfunction "PL20C_J3") (pintype "bidirectional"))
    )
    (net (code "76") (name "unconnected-(IC1-PL20D-PadK3)") (class "Default")
      (node (ref "IC1") (pin "K3") (pinfunction "PL20D_K3") (pintype "bidirectional"))
    )
    (net (code "77") (name "unconnected-(IC1-PL23A-PadJ1)") (class "Default")
      (node (ref "IC1") (pin "J1") (pinfunction "PL23A_J1") (pintype "bidirectional"))
    )
    (net (code "78") (name "unconnected-(IC1-PL23B-PadJ2)") (class "Default")
      (node (ref "IC1") (pin "J2") (pinfunction "PL23B_J2") (pintype "bidirectional"))
    )
    (net (code "79") (name "unconnected-(IC1-PL23C-PadK1)") (class "Default")
      (node (ref "IC1") (pin "K1") (pinfunction "PL23C_K1") (pintype "bidirectional"))
    )
    (net (code "80") (name "unconnected-(IC1-PL23D-PadK2)") (class "Default")
      (node (ref "IC1") (pin "K2") (pinfunction "PL23D_K2") (pintype "bidirectional"))
    )
    (net (code "81") (name "unconnected-(IC1-PL26A-PadL1)") (class "Default")
      (node (ref "IC1") (pin "L1") (pinfunction "PL26A_L1") (pintype "bidirectional"))
    )
    (net (code "82") (name "unconnected-(IC1-PL26B-PadL2)") (class "Default")
      (node (ref "IC1") (pin "L2") (pinfunction "PL26B_L2") (pintype "bidirectional"))
    )
    (net (code "83") (name "unconnected-(IC1-PL29A-PadK4)") (class "Default")
      (node (ref "IC1") (pin "K4") (pinfunction "PL29A_K4") (pintype "bidirectional"))
    )
    (net (code "84") (name "unconnected-(IC1-PL29B-PadK5)") (class "Default")
      (node (ref "IC1") (pin "K5") (pinfunction "PL29B_K5") (pintype "bidirectional"))
    )
    (net (code "85") (name "unconnected-(IC1-PL29C-PadL4)") (class "Default")
      (node (ref "IC1") (pin "L4") (pinfunction "PL29C_L4") (pintype "bidirectional"))
    )
    (net (code "86") (name "unconnected-(IC1-PL29D-PadL5)") (class "Default")
      (node (ref "IC1") (pin "L5") (pinfunction "PL29D_L5") (pintype "bidirectional"))
    )
    (net (code "87") (name "unconnected-(IC1-PL32C-PadL3)") (class "Default")
      (node (ref "IC1") (pin "L3") (pinfunction "PL32C_L3") (pintype "bidirectional"))
    )
    (net (code "88") (name "unconnected-(IC1-PL32D-PadM3)") (class "Default")
      (node (ref "IC1") (pin "M3") (pinfunction "PL32D_M3") (pintype "bidirectional"))
    )
    (net (code "89") (name "unconnected-(IC1-PL35A-PadP1)") (class "Default")
      (node (ref "IC1") (pin "P1") (pinfunction "PL35A_P1") (pintype "bidirectional"))
    )
    (net (code "90") (name "unconnected-(IC1-PL35B-PadR1)") (class "Default")
      (node (ref "IC1") (pin "R1") (pinfunction "PL35B_R1") (pintype "bidirectional"))
    )
    (net (code "91") (name "unconnected-(IC1-PL35C-PadM4)") (class "Default")
      (node (ref "IC1") (pin "M4") (pinfunction "PL35C_M4") (pintype "bidirectional"))
    )
    (net (code "92") (name "unconnected-(IC1-PL35D-PadN3)") (class "Default")
      (node (ref "IC1") (pin "N3") (pinfunction "PL35D_N3") (pintype "bidirectional"))
    )
    (net (code "93") (name "unconnected-(IC1-PL38A-PadN4)") (class "Default")
      (node (ref "IC1") (pin "N4") (pinfunction "PL38A_N4") (pintype "bidirectional"))
    )
    (net (code "94") (name "unconnected-(IC1-PL38B-PadP3)") (class "Default")
      (node (ref "IC1") (pin "P3") (pinfunction "PL38B_P3") (pintype "bidirectional"))
    )
    (net (code "95") (name "unconnected-(IC1-PL38C-PadR2)") (class "Default")
      (node (ref "IC1") (pin "R2") (pinfunction "PL38C_R2") (pintype "bidirectional"))
    )
    (net (code "96") (name "unconnected-(IC1-PL38D-PadT2)") (class "Default")
      (node (ref "IC1") (pin "T2") (pinfunction "PL38D_T2") (pintype "bidirectional"))
    )
    (net (code "97") (name "unconnected-(IC1-PL41A-PadP4)") (class "Default")
      (node (ref "IC1") (pin "P4") (pinfunction "PL41A_P4") (pintype "bidirectional"))
    )
    (net (code "98") (name "unconnected-(IC1-PL41B-PadR3)") (class "Default")
      (node (ref "IC1") (pin "R3") (pinfunction "PL41B_R3") (pintype "bidirectional"))
    )
    (net (code "99") (name "unconnected-(IC1-PL41C-PadR4)") (class "Default")
      (node (ref "IC1") (pin "R4") (pinfunction "PL41C_R4") (pintype "bidirectional"))
    )
    (net (code "100") (name "unconnected-(IC1-PL41D-PadT3)") (class "Default")
      (node (ref "IC1") (pin "T3") (pinfunction "PL41D_T3") (pintype "bidirectional"))
    )
    (net (code "101") (name "unconnected-(IC1-PL44A-PadR5)") (class "Default")
      (node (ref "IC1") (pin "R5") (pinfunction "PL44A_R5") (pintype "bidirectional"))
    )
    (net (code "102") (name "unconnected-(IC1-PL44B-PadT4)") (class "Default")
      (node (ref "IC1") (pin "T4") (pinfunction "PL44B_T4") (pintype "bidirectional"))
    )
    (net (code "103") (name "unconnected-(IC1-PL44C-PadM5)") (class "Default")
      (node (ref "IC1") (pin "M5") (pinfunction "PL44C_M5") (pintype "bidirectional"))
    )
    (net (code "104") (name "unconnected-(IC1-PL44D-PadN5)") (class "Default")
      (node (ref "IC1") (pin "N5") (pinfunction "PL44D_N5") (pintype "bidirectional"))
    )
    (net (code "105") (name "unconnected-(IC1-PL47A-PadM6)") (class "Default")
      (node (ref "IC1") (pin "M6") (pinfunction "PL47A_M6") (pintype "bidirectional"))
    )
    (net (code "106") (name "unconnected-(IC1-PL47B-PadN6)") (class "Default")
      (node (ref "IC1") (pin "N6") (pinfunction "PL47B_N6") (pintype "bidirectional"))
    )
    (net (code "107") (name "unconnected-(IC1-PL47C-PadP6)") (class "Default")
      (node (ref "IC1") (pin "P6") (pinfunction "PL47C_P6") (pintype "bidirectional"))
    )
    (net (code "108") (name "unconnected-(IC1-PL47D-PadP5)") (class "Default")
      (node (ref "IC1") (pin "P5") (pinfunction "PL47D_P5") (pintype "bidirectional"))
    )
    (net (code "109") (name "unconnected-(IC1-PR2B-PadB15)") (class "Default")
      (node (ref "IC1") (pin "B15") (pinfunction "PR2B_B15") (pintype "bidirectional"))
    )
    (net (code "110") (name "unconnected-(IC1-PR2C-PadC14)") (class "Default")
      (node (ref "IC1") (pin "C14") (pinfunction "PR2C_C14") (pintype "bidirectional"))
    )
    (net (code "111") (name "unconnected-(IC1-PR2D-PadD14)") (class "Default")
      (node (ref "IC1") (pin "D14") (pinfunction "PR2D_D14") (pintype "bidirectional"))
    )
    (net (code "112") (name "unconnected-(IC1-PR5C-PadE14)") (class "Default")
      (node (ref "IC1") (pin "E14") (pinfunction "PR5C_E14") (pintype "bidirectional"))
    )
    (net (code "113") (name "unconnected-(IC1-PR5D-PadF14)") (class "Default")
      (node (ref "IC1") (pin "F14") (pinfunction "PR5D_F14") (pintype "bidirectional"))
    )
    (net (code "114") (name "unconnected-(IC1-PR8C-PadF13)") (class "Default")
      (node (ref "IC1") (pin "F13") (pinfunction "PR8C_F13") (pintype "bidirectional"))
    )
    (net (code "115") (name "unconnected-(IC1-PR8D-PadF12)") (class "Default")
      (node (ref "IC1") (pin "F12") (pinfunction "PR8D_F12") (pintype "bidirectional"))
    )
    (net (code "116") (name "unconnected-(IC1-PR11A-PadG12)") (class "Default")
      (node (ref "IC1") (pin "G12") (pinfunction "PR11A_G12") (pintype "bidirectional"))
    )
    (net (code "117") (name "unconnected-(IC1-PR11B-PadG13)") (class "Default")
      (node (ref "IC1") (pin "G13") (pinfunction "PR11B_G13") (pintype "bidirectional"))
    )
    (net (code "118") (name "unconnected-(IC1-PR11C-PadF15)") (class "Default")
      (node (ref "IC1") (pin "F15") (pinfunction "PR11C_F15") (pintype "bidirectional"))
    )
    (net (code "119") (name "unconnected-(IC1-PR11D-PadE16)") (class "Default")
      (node (ref "IC1") (pin "E16") (pinfunction "PR11D_E16") (pintype "bidirectional"))
    )
    (net (code "120") (name "unconnected-(IC1-PR14A-PadF16)") (class "Default")
      (node (ref "IC1") (pin "F16") (pinfunction "PR14A_F16") (pintype "bidirectional"))
    )
    (net (code "121") (name "unconnected-(IC1-PR14B-PadG15)") (class "Default")
      (node (ref "IC1") (pin "G15") (pinfunction "PR14B_G15") (pintype "bidirectional"))
    )
    (net (code "122") (name "unconnected-(IC1-PR14C-PadG14)") (class "Default")
      (node (ref "IC1") (pin "G14") (pinfunction "PR14C_G14") (pintype "bidirectional"))
    )
    (net (code "123") (name "unconnected-(IC1-PR14D-PadH14)") (class "Default")
      (node (ref "IC1") (pin "H14") (pinfunction "PR14D_H14") (pintype "bidirectional"))
    )
    (net (code "124") (name "unconnected-(IC1-PR17A-PadH12)") (class "Default")
      (node (ref "IC1") (pin "H12") (pinfunction "PR17A_H12") (pintype "bidirectional"))
    )
    (net (code "125") (name "unconnected-(IC1-PR17B-PadH13)") (class "Default")
      (node (ref "IC1") (pin "H13") (pinfunction "PR17B_H13") (pintype "bidirectional"))
    )
    (net (code "126") (name "unconnected-(IC1-PR17C-PadJ13)") (class "Default")
      (node (ref "IC1") (pin "J13") (pinfunction "PR17C_J13") (pintype "bidirectional"))
    )
    (net (code "127") (name "unconnected-(IC1-PR17D-PadJ12)") (class "Default")
      (node (ref "IC1") (pin "J12") (pinfunction "PR17D_J12") (pintype "bidirectional"))
    )
    (net (code "128") (name "unconnected-(IC1-PR20A-PadG16)") (class "Default")
      (node (ref "IC1") (pin "G16") (pinfunction "PR20A_G16") (pintype "bidirectional"))
    )
    (net (code "129") (name "unconnected-(IC1-PR20B-PadH15)") (class "Default")
      (node (ref "IC1") (pin "H15") (pinfunction "PR20B_H15") (pintype "bidirectional"))
    )
    (net (code "130") (name "unconnected-(IC1-PR20C-PadJ14)") (class "Default")
      (node (ref "IC1") (pin "J14") (pinfunction "PR20C_J14") (pintype "bidirectional"))
    )
    (net (code "131") (name "unconnected-(IC1-PR20D-PadK14)") (class "Default")
      (node (ref "IC1") (pin "K14") (pinfunction "PR20D_K14") (pintype "bidirectional"))
    )
    (net (code "132") (name "unconnected-(IC1-PR23C-PadK16)") (class "Default")
      (node (ref "IC1") (pin "K16") (pinfunction "PR23C_K16") (pintype "bidirectional"))
    )
    (net (code "133") (name "unconnected-(IC1-PR23D-PadK15)") (class "Default")
      (node (ref "IC1") (pin "K15") (pinfunction "PR23D_K15") (pintype "bidirectional"))
    )
    (net (code "134") (name "unconnected-(IC1-PR26A-PadL16)") (class "Default")
      (node (ref "IC1") (pin "L16") (pinfunction "PR26A_L16") (pintype "bidirectional"))
    )
    (net (code "135") (name "unconnected-(IC1-PR26B-PadL15)") (class "Default")
      (node (ref "IC1") (pin "L15") (pinfunction "PR26B_L15") (pintype "bidirectional"))
    )
    (net (code "136") (name "unconnected-(IC1-PR29A-PadK13)") (class "Default")
      (node (ref "IC1") (pin "K13") (pinfunction "PR29A_K13") (pintype "bidirectional"))
    )
    (net (code "137") (name "unconnected-(IC1-PR29B-PadK12)") (class "Default")
      (node (ref "IC1") (pin "K12") (pinfunction "PR29B_K12") (pintype "bidirectional"))
    )
    (net (code "138") (name "unconnected-(IC1-PR29C-PadL13)") (class "Default")
      (node (ref "IC1") (pin "L13") (pinfunction "PR29C_L13") (pintype "bidirectional"))
    )
    (net (code "139") (name "unconnected-(IC1-PR29D-PadL12)") (class "Default")
      (node (ref "IC1") (pin "L12") (pinfunction "PR29D_L12") (pintype "bidirectional"))
    )
    (net (code "140") (name "unconnected-(IC1-PR32A-PadN16)") (class "Default")
      (node (ref "IC1") (pin "N16") (pinfunction "PR32A_N16") (pintype "bidirectional"))
    )
    (net (code "141") (name "unconnected-(IC1-PR32B-PadP15)") (class "Default")
      (node (ref "IC1") (pin "P15") (pinfunction "PR32B_P15") (pintype "bidirectional"))
    )
    (net (code "142") (name "unconnected-(IC1-PR32C-PadL14)") (class "Default")
      (node (ref "IC1") (pin "L14") (pinfunction "PR32C_L14") (pintype "bidirectional"))
    )
    (net (code "143") (name "unconnected-(IC1-PR32D-PadM14)") (class "Default")
      (node (ref "IC1") (pin "M14") (pinfunction "PR32D_M14") (pintype "bidirectional"))
    )
    (net (code "144") (name "unconnected-(IC1-PR35C-PadM13)") (class "Default")
      (node (ref "IC1") (pin "M13") (pinfunction "PR35C_M13") (pintype "bidirectional"))
    )
    (net (code "145") (name "unconnected-(IC1-PR35D-PadN14)") (class "Default")
      (node (ref "IC1") (pin "N14") (pinfunction "PR35D_N14") (pintype "bidirectional"))
    )
    (net (code "146") (name "unconnected-(IC1-PR38A-PadN13)") (class "Default")
      (node (ref "IC1") (pin "N13") (pinfunction "PR38A_N13") (pintype "bidirectional"))
    )
    (net (code "147") (name "unconnected-(IC1-PR38B-PadP14)") (class "Default")
      (node (ref "IC1") (pin "P14") (pinfunction "PR38B_P14") (pintype "bidirectional"))
    )
    (net (code "148") (name "unconnected-(IC1-PR38C-PadR15)") (class "Default")
      (node (ref "IC1") (pin "R15") (pinfunction "PR38C_R15") (pintype "bidirectional"))
    )
    (net (code "149") (name "unconnected-(IC1-PR38D-PadT15)") (class "Default")
      (node (ref "IC1") (pin "T15") (pinfunction "PR38D_T15") (pintype "bidirectional"))
    )
    (net (code "150") (name "unconnected-(IC1-PR41A-PadP13)") (class "Default")
      (node (ref "IC1") (pin "P13") (pinfunction "PR41A_P13") (pintype "bidirectional"))
    )
    (net (code "151") (name "unconnected-(IC1-PR41B-PadR14)") (class "Default")
      (node (ref "IC1") (pin "R14") (pinfunction "PR41B_R14") (pintype "bidirectional"))
    )
    (net (code "152") (name "unconnected-(IC1-PR41C-PadR13)") (class "Default")
      (node (ref "IC1") (pin "R13") (pinfunction "PR41C_R13") (pintype "bidirectional"))
    )
    (net (code "153") (name "unconnected-(IC1-PR41D-PadT14)") (class "Default")
      (node (ref "IC1") (pin "T14") (pinfunction "PR41D_T14") (pintype "bidirectional"))
    )
    (net (code "154") (name "unconnected-(IC1-PR44A-PadR12)") (class "Default")
      (node (ref "IC1") (pin "R12") (pinfunction "PR44A_R12") (pintype "bidirectional"))
    )
    (net (code "155") (name "unconnected-(IC1-PR44B-PadT13)") (class "Default")
      (node (ref "IC1") (pin "T13") (pinfunction "PR44B_T13") (pintype "bidirectional"))
    )
    (net (code "156") (name "unconnected-(IC1-PR44C-PadM12)") (class "Default")
      (node (ref "IC1") (pin "M12") (pinfunction "PR44C_M12") (pintype "bidirectional"))
    )
    (net (code "157") (name "unconnected-(IC1-PR44D-PadN12)") (class "Default")
      (node (ref "IC1") (pin "N12") (pinfunction "PR44D_N12") (pintype "bidirectional"))
    )
    (net (code "158") (name "unconnected-(IC1-PR47A-PadM11)") (class "Default")
      (node (ref "IC1") (pin "M11") (pinfunction "PR47A_M11") (pintype "bidirectional"))
    )
    (net (code "159") (name "unconnected-(IC1-PR47B-PadN11)") (class "Default")
      (node (ref "IC1") (pin "N11") (pinfunction "PR47B_N11") (pintype "bidirectional"))
    )
    (net (code "160") (name "unconnected-(IC1-PR47C-PadP11)") (class "Default")
      (node (ref "IC1") (pin "P11") (pinfunction "PR47C_P11") (pintype "bidirectional"))
    )
    (net (code "161") (name "unconnected-(IC1-PR47D-PadP12)") (class "Default")
      (node (ref "IC1") (pin "P12") (pinfunction "PR47D_P12") (pintype "bidirectional"))
    )
    (net (code "162") (name "unconnected-(IC1-PT4B-PadB3)") (class "Default")
      (node (ref "IC1") (pin "B3") (pinfunction "PT4B_B3") (pintype "bidirectional"))
    )
    (net (code "163") (name "unconnected-(IC1-PT6A-PadA3)") (class "Default")
      (node (ref "IC1") (pin "A3") (pinfunction "PT6A_A3") (pintype "bidirectional"))
    )
    (net (code "164") (name "unconnected-(IC1-PT6B-PadA4)") (class "Default")
      (node (ref "IC1") (pin "A4") (pinfunction "PT6B_A4") (pintype "bidirectional"))
    )
    (net (code "165") (name "unconnected-(IC1-PT9A-PadE4)") (class "Default")
      (node (ref "IC1") (pin "E4") (pinfunction "PT9A_E4") (pintype "bidirectional"))
    )
    (net (code "166") (name "unconnected-(IC1-PT9B-PadD4)") (class "Default")
      (node (ref "IC1") (pin "D4") (pinfunction "PT9B_D4") (pintype "bidirectional"))
    )
    (net (code "167") (name "unconnected-(IC1-PT11A-PadC4)") (class "Default")
      (node (ref "IC1") (pin "C4") (pinfunction "PT11A_C4") (pintype "bidirectional"))
    )
    (net (code "168") (name "unconnected-(IC1-PT11B-PadB4)") (class "Default")
      (node (ref "IC1") (pin "B4") (pinfunction "PT11B_B4") (pintype "bidirectional"))
    )
    (net (code "169") (name "unconnected-(IC1-PT13A-PadE5)") (class "Default")
      (node (ref "IC1") (pin "E5") (pinfunction "PT13A_E5") (pintype "bidirectional"))
    )
    (net (code "170") (name "unconnected-(IC1-PT13B-PadD5)") (class "Default")
      (node (ref "IC1") (pin "D5") (pinfunction "PT13B_D5") (pintype "bidirectional"))
    )
    (net (code "171") (name "unconnected-(IC1-PT15A-PadC5)") (class "Default")
      (node (ref "IC1") (pin "C5") (pinfunction "PT15A_C5") (pintype "bidirectional"))
    )
    (net (code "172") (name "unconnected-(IC1-PT15B-PadB5)") (class "Default")
      (node (ref "IC1") (pin "B5") (pinfunction "PT15B_B5") (pintype "bidirectional"))
    )
    (net (code "173") (name "unconnected-(IC1-PT18A-PadA5)") (class "Default")
      (node (ref "IC1") (pin "A5") (pinfunction "PT18A_A5") (pintype "bidirectional"))
    )
    (net (code "174") (name "unconnected-(IC1-PT18B-PadA6)") (class "Default")
      (node (ref "IC1") (pin "A6") (pinfunction "PT18B_A6") (pintype "bidirectional"))
    )
    (net (code "175") (name "unconnected-(IC1-PT20A-PadE6)") (class "Default")
      (node (ref "IC1") (pin "E6") (pinfunction "PT20A_E6") (pintype "bidirectional"))
    )
    (net (code "176") (name "unconnected-(IC1-PT20B-PadD6)") (class "Default")
      (node (ref "IC1") (pin "D6") (pinfunction "PT20B_D6") (pintype "bidirectional"))
    )
    (net (code "177") (name "unconnected-(IC1-PT22A-PadC6)") (class "Default")
      (node (ref "IC1") (pin "C6") (pinfunction "PT22A_C6") (pintype "bidirectional"))
    )
    (net (code "178") (name "unconnected-(IC1-PT22B-PadB6)") (class "Default")
      (node (ref "IC1") (pin "B6") (pinfunction "PT22B_B6") (pintype "bidirectional"))
    )
    (net (code "179") (name "unconnected-(IC1-PT24A-PadE7)") (class "Default")
      (node (ref "IC1") (pin "E7") (pinfunction "PT24A_E7") (pintype "bidirectional"))
    )
    (net (code "180") (name "unconnected-(IC1-PT24B-PadD7)") (class "Default")
      (node (ref "IC1") (pin "D7") (pinfunction "PT24B_D7") (pintype "bidirectional"))
    )
    (net (code "181") (name "unconnected-(IC1-PT27A-PadC7)") (class "Default")
      (node (ref "IC1") (pin "C7") (pinfunction "PT27A_C7") (pintype "bidirectional"))
    )
    (net (code "182") (name "unconnected-(IC1-PT27B-PadB7)") (class "Default")
      (node (ref "IC1") (pin "B7") (pinfunction "PT27B_B7") (pintype "bidirectional"))
    )
    (net (code "183") (name "unconnected-(IC1-PT29A-PadA7)") (class "Default")
      (node (ref "IC1") (pin "A7") (pinfunction "PT29A_A7") (pintype "bidirectional"))
    )
    (net (code "184") (name "unconnected-(IC1-PT29B-PadA8)") (class "Default")
      (node (ref "IC1") (pin "A8") (pinfunction "PT29B_A8") (pintype "bidirectional"))
    )
    (net (code "185") (name "unconnected-(IC1-PT33A-PadE8)") (class "Default")
      (node (ref "IC1") (pin "E8") (pinfunction "PT33A_E8") (pintype "bidirectional"))
    )
    (net (code "186") (name "unconnected-(IC1-PT33B-PadD8)") (class "Default")
      (node (ref "IC1") (pin "D8") (pinfunction "PT33B_D8") (pintype "bidirectional"))
    )
    (net (code "187") (name "unconnected-(IC1-PT35A-PadC8)") (class "Default")
      (node (ref "IC1") (pin "C8") (pinfunction "PT35A_C8") (pintype "bidirectional"))
    )
    (net (code "188") (name "unconnected-(IC1-PT35B-PadB8)") (class "Default")
      (node (ref "IC1") (pin "B8") (pinfunction "PT35B_B8") (pintype "bidirectional"))
    )
    (net (code "189") (name "unconnected-(IC1-PT38A-PadB9)") (class "Default")
      (node (ref "IC1") (pin "B9") (pinfunction "PT38A_B9") (pintype "bidirectional"))
    )
    (net (code "190") (name "unconnected-(IC1-PT38B-PadC9)") (class "Default")
      (node (ref "IC1") (pin "C9") (pinfunction "PT38B_C9") (pintype "bidirectional"))
    )
    (net (code "191") (name "unconnected-(IC1-PT40A-PadD9)") (class "Default")
      (node (ref "IC1") (pin "D9") (pinfunction "PT40A_D9") (pintype "bidirectional"))
    )
    (net (code "192") (name "unconnected-(IC1-PT40B-PadE9)") (class "Default")
      (node (ref "IC1") (pin "E9") (pinfunction "PT40B_E9") (pintype "bidirectional"))
    )
    (net (code "193") (name "unconnected-(IC1-PT42A-PadA9)") (class "Default")
      (node (ref "IC1") (pin "A9") (pinfunction "PT42A_A9") (pintype "bidirectional"))
    )
    (net (code "194") (name "unconnected-(IC1-PT42B-PadA10)") (class "Default")
      (node (ref "IC1") (pin "A10") (pinfunction "PT42B_A10") (pintype "bidirectional"))
    )
    (net (code "195") (name "unconnected-(IC1-PT44A-PadB10)") (class "Default")
      (node (ref "IC1") (pin "B10") (pinfunction "PT44A_B10") (pintype "bidirectional"))
    )
    (net (code "196") (name "unconnected-(IC1-PT44B-PadC10)") (class "Default")
      (node (ref "IC1") (pin "C10") (pinfunction "PT44B_C10") (pintype "bidirectional"))
    )
    (net (code "197") (name "unconnected-(IC1-PT47A-PadD10)") (class "Default")
      (node (ref "IC1") (pin "D10") (pinfunction "PT47A_D10") (pintype "bidirectional"))
    )
    (net (code "198") (name "unconnected-(IC1-PT47B-PadE10)") (class "Default")
      (node (ref "IC1") (pin "E10") (pinfunction "PT47B_E10") (pintype "bidirectional"))
    )
    (net (code "199") (name "unconnected-(IC1-PT49A-PadB11)") (class "Default")
      (node (ref "IC1") (pin "B11") (pinfunction "PT49A_B11") (pintype "bidirectional"))
    )
    (net (code "200") (name "unconnected-(IC1-PT49B-PadC11)") (class "Default")
      (node (ref "IC1") (pin "C11") (pinfunction "PT49B_C11") (pintype "bidirectional"))
    )
    (net (code "201") (name "unconnected-(IC1-PT51A-PadD11)") (class "Default")
      (node (ref "IC1") (pin "D11") (pinfunction "PT51A_D11") (pintype "bidirectional"))
    )
    (net (code "202") (name "unconnected-(IC1-PT51B-PadE11)") (class "Default")
      (node (ref "IC1") (pin "E11") (pinfunction "PT51B_E11") (pintype "bidirectional"))
    )
    (net (code "203") (name "unconnected-(IC1-PT53A-PadA11)") (class "Default")
      (node (ref "IC1") (pin "A11") (pinfunction "PT53A_A11") (pintype "bidirectional"))
    )
    (net (code "204") (name "unconnected-(IC1-PT53B-PadA12)") (class "Default")
      (node (ref "IC1") (pin "A12") (pinfunction "PT53B_A12") (pintype "bidirectional"))
    )
    (net (code "205") (name "unconnected-(IC1-PT56A-PadB12)") (class "Default")
      (node (ref "IC1") (pin "B12") (pinfunction "PT56A_B12") (pintype "bidirectional"))
    )
    (net (code "206") (name "unconnected-(IC1-PT56B-PadC12)") (class "Default")
      (node (ref "IC1") (pin "C12") (pinfunction "PT56B_C12") (pintype "bidirectional"))
    )
    (net (code "207") (name "unconnected-(IC1-PT58A-PadD12)") (class "Default")
      (node (ref "IC1") (pin "D12") (pinfunction "PT58A_D12") (pintype "bidirectional"))
    )
    (net (code "208") (name "unconnected-(IC1-PT58B-PadE12)") (class "Default")
      (node (ref "IC1") (pin "E12") (pinfunction "PT58B_E12") (pintype "bidirectional"))
    )
    (net (code "209") (name "unconnected-(IC1-PT60A-PadB13)") (class "Default")
      (node (ref "IC1") (pin "B13") (pinfunction "PT60A_B13") (pintype "bidirectional"))
    )
    (net (code "210") (name "unconnected-(IC1-PT60B-PadC13)") (class "Default")
      (node (ref "IC1") (pin "C13") (pinfunction "PT60B_C13") (pintype "bidirectional"))
    )
    (net (code "211") (name "unconnected-(IC1-PT62A-PadD13)") (class "Default")
      (node (ref "IC1") (pin "D13") (pinfunction "PT62A_D13") (pintype "bidirectional"))
    )
    (net (code "212") (name "unconnected-(IC1-PT62B-PadE13)") (class "Default")
      (node (ref "IC1") (pin "E13") (pinfunction "PT62B_E13") (pintype "bidirectional"))
    )
    (net (code "213") (name "unconnected-(IC1-PT65A-PadA13)") (class "Default")
      (node (ref "IC1") (pin "A13") (pinfunction "PT65A_A13") (pintype "bidirectional"))
    )
    (net (code "214") (name "unconnected-(IC1-PT65B-PadA14)") (class "Default")
      (node (ref "IC1") (pin "A14") (pinfunction "PT65B_A14") (pintype "bidirectional"))
    )
    (net (code "215") (name "unconnected-(IC1-PT67A-PadB14)") (class "Default")
      (node (ref "IC1") (pin "B14") (pinfunction "PT67A_B14") (pintype "bidirectional"))
    )
    (net (code "216") (name "unconnected-(IC1-PT67B-PadA15)") (class "Default")
      (node (ref "IC1") (pin "A15") (pinfunction "PT67B_A15") (pintype "bidirectional"))
    )
    (net (code "217") (name "unconnected-(J2-Pad1)") (class "Default")
      (node (ref "J2") (pin "1") (pinfunction "1_1") (pintype "bidirectional"))
    )
    (net (code "218") (name "unconnected-(J2-Pad6)") (class "Default")
      (node (ref "J2") (pin "6") (pinfunction "6_6") (pintype "bidirectional"))
    )
    (net (code "219") (name "unconnected-(LED4-DOUT-Pad1)") (class "Default")
      (node (ref "LED4") (pin "1") (pinfunction "DOUT_1") (pintype "bidirectional"))
    )
    (net (code "220") (name "unconnected-(U1-BYPASS-Pad4)") (class "Default")
      (node (ref "U1") (pin "4") (pinfunction "BYPASS_4") (pintype "bidirectional"))
    )
    (net (code "221") (name "unconnected-(U2-BYPASS-Pad4)") (class "Default")
      (node (ref "U2") (pin "4") (pinfunction "BYPASS_4") (pintype "bidirectional"))
    )
    (net (code "222") (name "unconnected-(U6-BYPASS-Pad4)") (class "Default")
      (node (ref "U6") (pin "4") (pinfunction "BYPASS_4") (pintype "bidirectional"))
    )
    (net (code "223") (name "unconnected-(U9-HOLD-Pad7)") (class "Default")
      (node (ref "U9") (pin "7") (pinfunction "HOLD_7") (pintype "bidirectional"))
    )
    (net (code "224") (name "unconnected-(U9-WP-Pad3)") (class "Default")
      (node (ref "U9") (pin "3") (pinfunction "WP_3") (pintype "bidirectional"))
    )
  )
)
